# Sheet1.net
KiCad netlist of a schematic drawn in Altium Designer
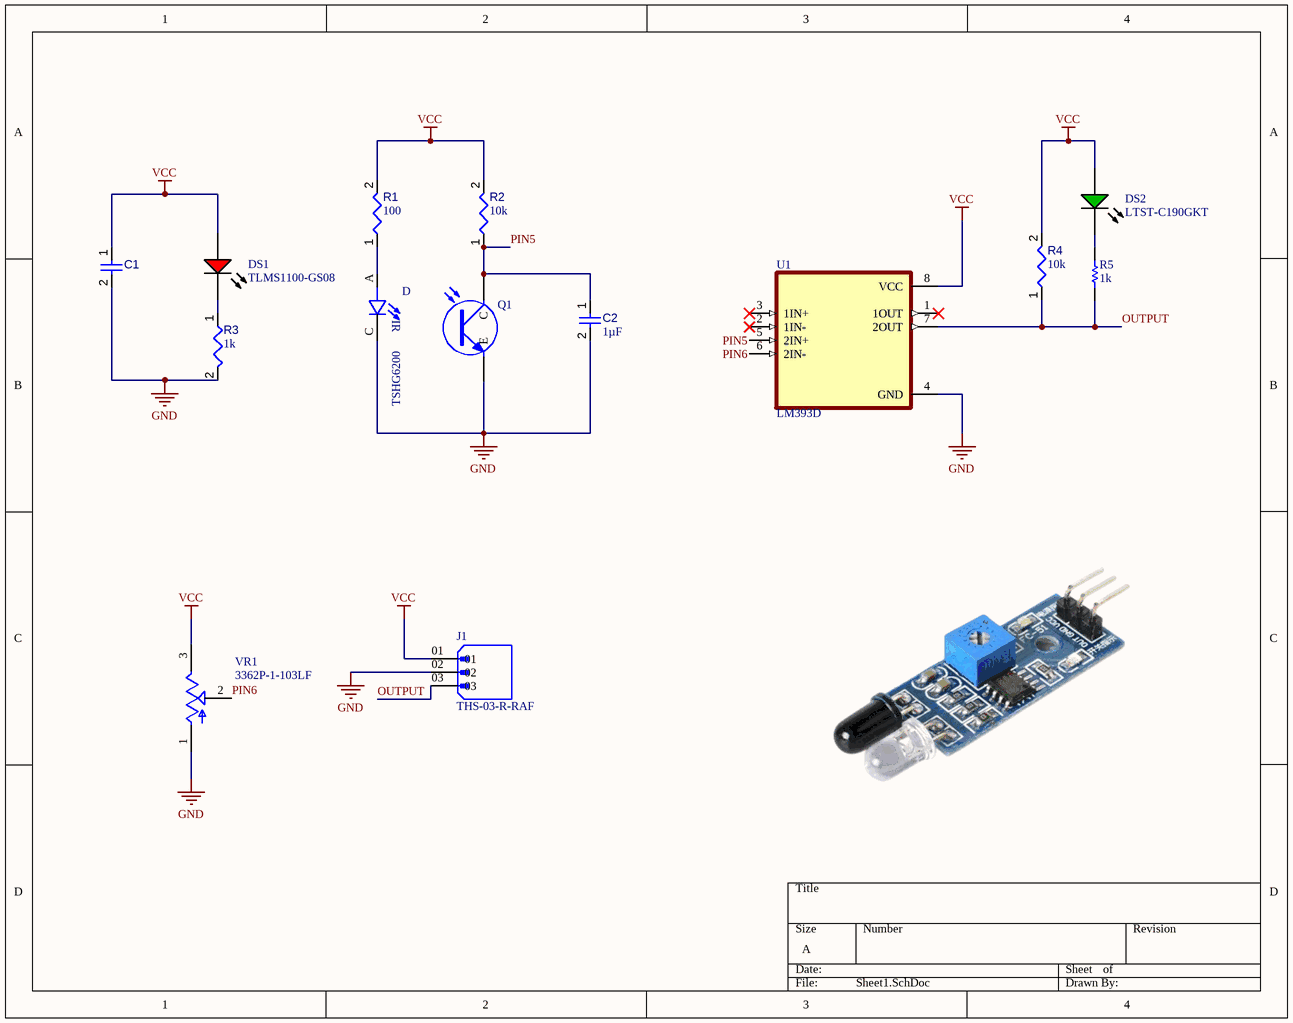
[diagram p0: Sheet1.SchDoc]

(export (version "E")
  (design (tool "Eeschema 10.0.6"))
  (components
    (comp (ref "C1")
      (value "Capacitor 1 uF +/- 10% 25 V 0805")
      (footprint "CAPC2013X145X50ML20T25")
      (description "Chip Capacitor, 1 uF, +/-10%, 25 V, 0805 (2012 Metric)")
      (fields (field (name "TOLERANCE") "10%"))
      (libsource (lib "Med khalil khlifi") (part "CAP-NP-2"))
    )
    (comp (ref "C2")
      (value "1µF")
      (footprint "CAPC2013X145X50ML20T25")
      (description "Chip Capacitor, 1 uF, +/-10%, 25 V, 0805 (2012 Metric)")
      (fields (field (name "TOLERANCE") "10%") (field (name "Comment") "Capacitor 1 uF +/- 10% 25 V 0805"))
      (libsource (lib "Med khalil khlifi") (part "CAP-NP-2"))
    )
    (comp (ref "D")
      (value "TSHG6200")
      (footprint "LEDRD254W55D595H900")
      (description "Infrared Emitter 850nm 1800mW/sr Circular Top Mount 2-Pin T-1 3/4")
      (fields
        (field (name "MF") "Vishay")
        (field (name "BUYPART") "https://www.snapeda.com/parts/TSHG6200/Vishay/view-part/3623411/?ref=eda")
      )
      (libsource (lib "IR Transmitter LED") (part "TSHG6200"))
    )
    (comp (ref "DS1")
      (value "TLMS1100-GS08")
      (footprint "VISH-TLMX1100_V")
      (description "Red Led, 20mA, 2.1 V, -40 to 100 degC, 2-Pin SMD (0603), RoHS, Tape and Reel")
      (fields (field (name "MANUFACTURER") "Vishay Semiconductor") (field (name "POWER") "90mW"))
      (libsource (lib "Med khalil khlifi") (part "LED-RED-AK-2"))
    )
    (comp (ref "DS2")
      (value "LTST-C190GKT")
      (footprint "LTST-C190GKT_V")
      (description "LED Uni-Color Green, 100 mW, 30 mA, -55 to 85 degC, 2-Pin SMD, RoHS, Tape and Reel")
      (fields (field (name "POWER") "100mW") (field (name "MANUFACTURER") "Lite-On"))
      (libsource (lib "Med khalil khlifi") (part "LED-GREEN-AK-2"))
    )
    (comp (ref "J1")
      (value "THS-03-R-RAF")
      (footprint "VALCON_THS-03-R-RAF")
      (libsource (lib "Header 3") (part "THS-03-R-RAF"))
    )
    (comp (ref "Q1")
      (value "1540051NC2590")
      (footprint "WL-TTRB_D5H8.7")
      (description "WL-TTRB THT Phototransistor Round Black, D5H8.7mm, 700-1100nm, 1.5mA, 25°")
      (fields (field (name "MANUFACTURER") "Wurth Elektronik"))
      (libsource (lib "PHOTOTRANSISTOR") (part "1540051NC2590"))
    )
    (comp (ref "R1")
      (value "100")
      (footprint "RESC0402(1005)_L")
      (description "Chip Resistor, 100 Ohms, +/-1 %, 63 mW, -55 to 155 degC, 0402")
      (fields (field (name "POWER") "63mW") (field (name "TOLERANCE") "1%"))
      (libsource (lib "Med khalil khlifi") (part "RES-2"))
    )
    (comp (ref "R2")
      (value "10k")
      (footprint "RESC1608X55X25ML10T15")
      (description "Chip Resistor, 10 KOhm, +/- 1%, 01 W, -55 to 155 degC, 0603 (1608 Metric)")
      (fields (field (name "POWER") "100mW") (field (name "TOLERANCE") "1%"))
      (libsource (lib "Med khalil khlifi") (part "RES-2"))
    )
    (comp (ref "R3")
      (value "1k")
      (footprint "RESC0402(1005)_L")
      (description "Chip Resistor, 1 kOhms, +/-5 %, 63 mW, -55 to 155 degC, 0402")
      (fields (field (name "TOLERANCE") "5%") (field (name "POWER") "63mW"))
      (libsource (lib "Med khalil khlifi") (part "RES-2"))
    )
    (comp (ref "R4")
      (value "10k")
      (footprint "RESC1608X55X25ML10T15")
      (description "Chip Resistor, 10 KOhm, +/- 1%, 01 W, -55 to 155 degC, 0603 (1608 Metric)")
      (fields (field (name "POWER") "100mW") (field (name "TOLERANCE") "1%"))
      (libsource (lib "Med khalil khlifi") (part "RES-2"))
    )
    (comp (ref "R5")
      (value "1k")
      (footprint "RESC1005X40X25ML05T05")
      (description "Chip Resistor, 1 KOhm, +/- 1%, 0.1 W, -55 to 155 degC, 0402 (1005 Metric)")
      (fields (field (name "POWER") "100mW") (field (name "TOLERANCE") "1%"))
      (libsource (lib "") (part "RES-2_1"))
    )
    (comp (ref "U1")
      (value "LM393D")
      (footprint "SOIC127P599X175-8N")
      (description "Dual differential comparator, commercial grade")
      (fields (field (name "MF") "Texas Instruments"))
      (libsource (lib "LM393D") (part "LM393D"))
    )
    (comp (ref "VR1")
      (value "3362P-1-103LF")
      (footprint "TRIM_3362P-1-103LF")
      (description "10 kOhms 0.5W, 1/2W PC Pins Through Hole Trimmer Potentiometer Cermet 1 Turn Top Adjustment")
      (fields (field (name "DIGI-KEY_PART_NUMBER") "3362P-103LF-ND") (field (name "MF") "Bourns"))
      (libsource (lib "Potentiometer") (part "3362P-1-103LF"))
    )
  )
  (nets
    (net (code "1") (name "/OUTPUT") (class "Default")
      (node (ref "J1") (pin "03") (pinfunction "03_03") (pintype "passive"))
      (node (ref "R4") (pin "1") (pinfunction "1_1") (pintype "passive"))
      (node (ref "R5") (pin "1") (pinfunction "1_1") (pintype "passive"))
      (node (ref "U1") (pin "7") (pinfunction "2OUT_7") (pintype "output"))
    )
    (net (code "2") (name "/PIN5") (class "Default")
      (node (ref "C2") (pin "1") (pinfunction "1_1") (pintype "passive"))
      (node (ref "Q1") (pin "1") (pinfunction "C_1") (pintype "passive"))
      (node (ref "R2") (pin "1") (pinfunction "1_1") (pintype "passive"))
      (node (ref "U1") (pin "5") (pinfunction "2IN+_5") (pintype "input"))
    )
    (net (code "3") (name "/PIN6") (class "Default")
      (node (ref "U1") (pin "6") (pinfunction "2IN-_6") (pintype "input"))
      (node (ref "VR1") (pin "2") (pinfunction "WIPER_2") (pintype "passive"))
    )
    (net (code "4") (name "GND") (class "Default")
      (node (ref "C1") (pin "2") (pinfunction "2_2") (pintype "passive"))
      (node (ref "C2") (pin "2") (pinfunction "2_2") (pintype "passive"))
      (node (ref "D") (pin "C") (pinfunction "C_C") (pintype "passive"))
      (node (ref "J1") (pin "02") (pinfunction "02_02") (pintype "passive"))
      (node (ref "Q1") (pin "2") (pinfunction "E_2") (pintype "passive"))
      (node (ref "R3") (pin "2") (pinfunction "2_2") (pintype "passive"))
      (node (ref "U1") (pin "4") (pinfunction "GND_4") (pintype "power_in"))
      (node (ref "VR1") (pin "1") (pinfunction "CCW_1") (pintype "passive"))
    )
    (net (code "5") (name "Net-(D-PadA)") (class "Default")
      (node (ref "D") (pin "A") (pinfunction "A_A") (pintype "passive"))
      (node (ref "R1") (pin "1") (pinfunction "1_1") (pintype "passive"))
    )
    (net (code "6") (name "Net-(DS1-K)") (class "Default")
      (node (ref "DS1") (pin "2") (pinfunction "K_2") (pintype "passive"))
      (node (ref "R3") (pin "1") (pinfunction "1_1") (pintype "passive"))
    )
    (net (code "7") (name "Net-(DS2-K)") (class "Default")
      (node (ref "DS2") (pin "2") (pinfunction "K_2") (pintype "passive"))
      (node (ref "R5") (pin "2") (pinfunction "2_2") (pintype "passive"))
    )
    (net (code "8") (name "VCC") (class "Default")
      (node (ref "C1") (pin "1") (pinfunction "1_1") (pintype "passive"))
      (node (ref "DS1") (pin "1") (pinfunction "A_1") (pintype "passive"))
      (node (ref "DS2") (pin "1") (pinfunction "A_1") (pintype "passive"))
      (node (ref "J1") (pin "01") (pinfunction "01_01") (pintype "passive"))
      (node (ref "R1") (pin "2") (pinfunction "2_2") (pintype "passive"))
      (node (ref "R2") (pin "2") (pinfunction "2_2") (pintype "passive"))
      (node (ref "R4") (pin "2") (pinfunction "2_2") (pintype "passive"))
      (node (ref "U1") (pin "8") (pinfunction "VCC_8") (pintype "power_in"))
      (node (ref "VR1") (pin "3") (pinfunction "CW_3") (pintype "passive"))
    )
    (net (code "9") (name "unconnected-(U1-1IN+-Pad3)") (class "Default")
      (node (ref "U1") (pin "3") (pinfunction "1IN+_3") (pintype "input+no_connect"))
    )
    (net (code "10") (name "unconnected-(U1-1IN--Pad2)") (class "Default")
      (node (ref "U1") (pin "2") (pinfunction "1IN-_2") (pintype "input+no_connect"))
    )
    (net (code "11") (name "unconnected-(U1-1OUT-Pad1)") (class "Default")
      (node (ref "U1") (pin "1") (pinfunction "1OUT_1") (pintype "output+no_connect"))
    )
  )
)
